# pc_kalam.net
KiCad netlist of a schematic drawn in EAGLE
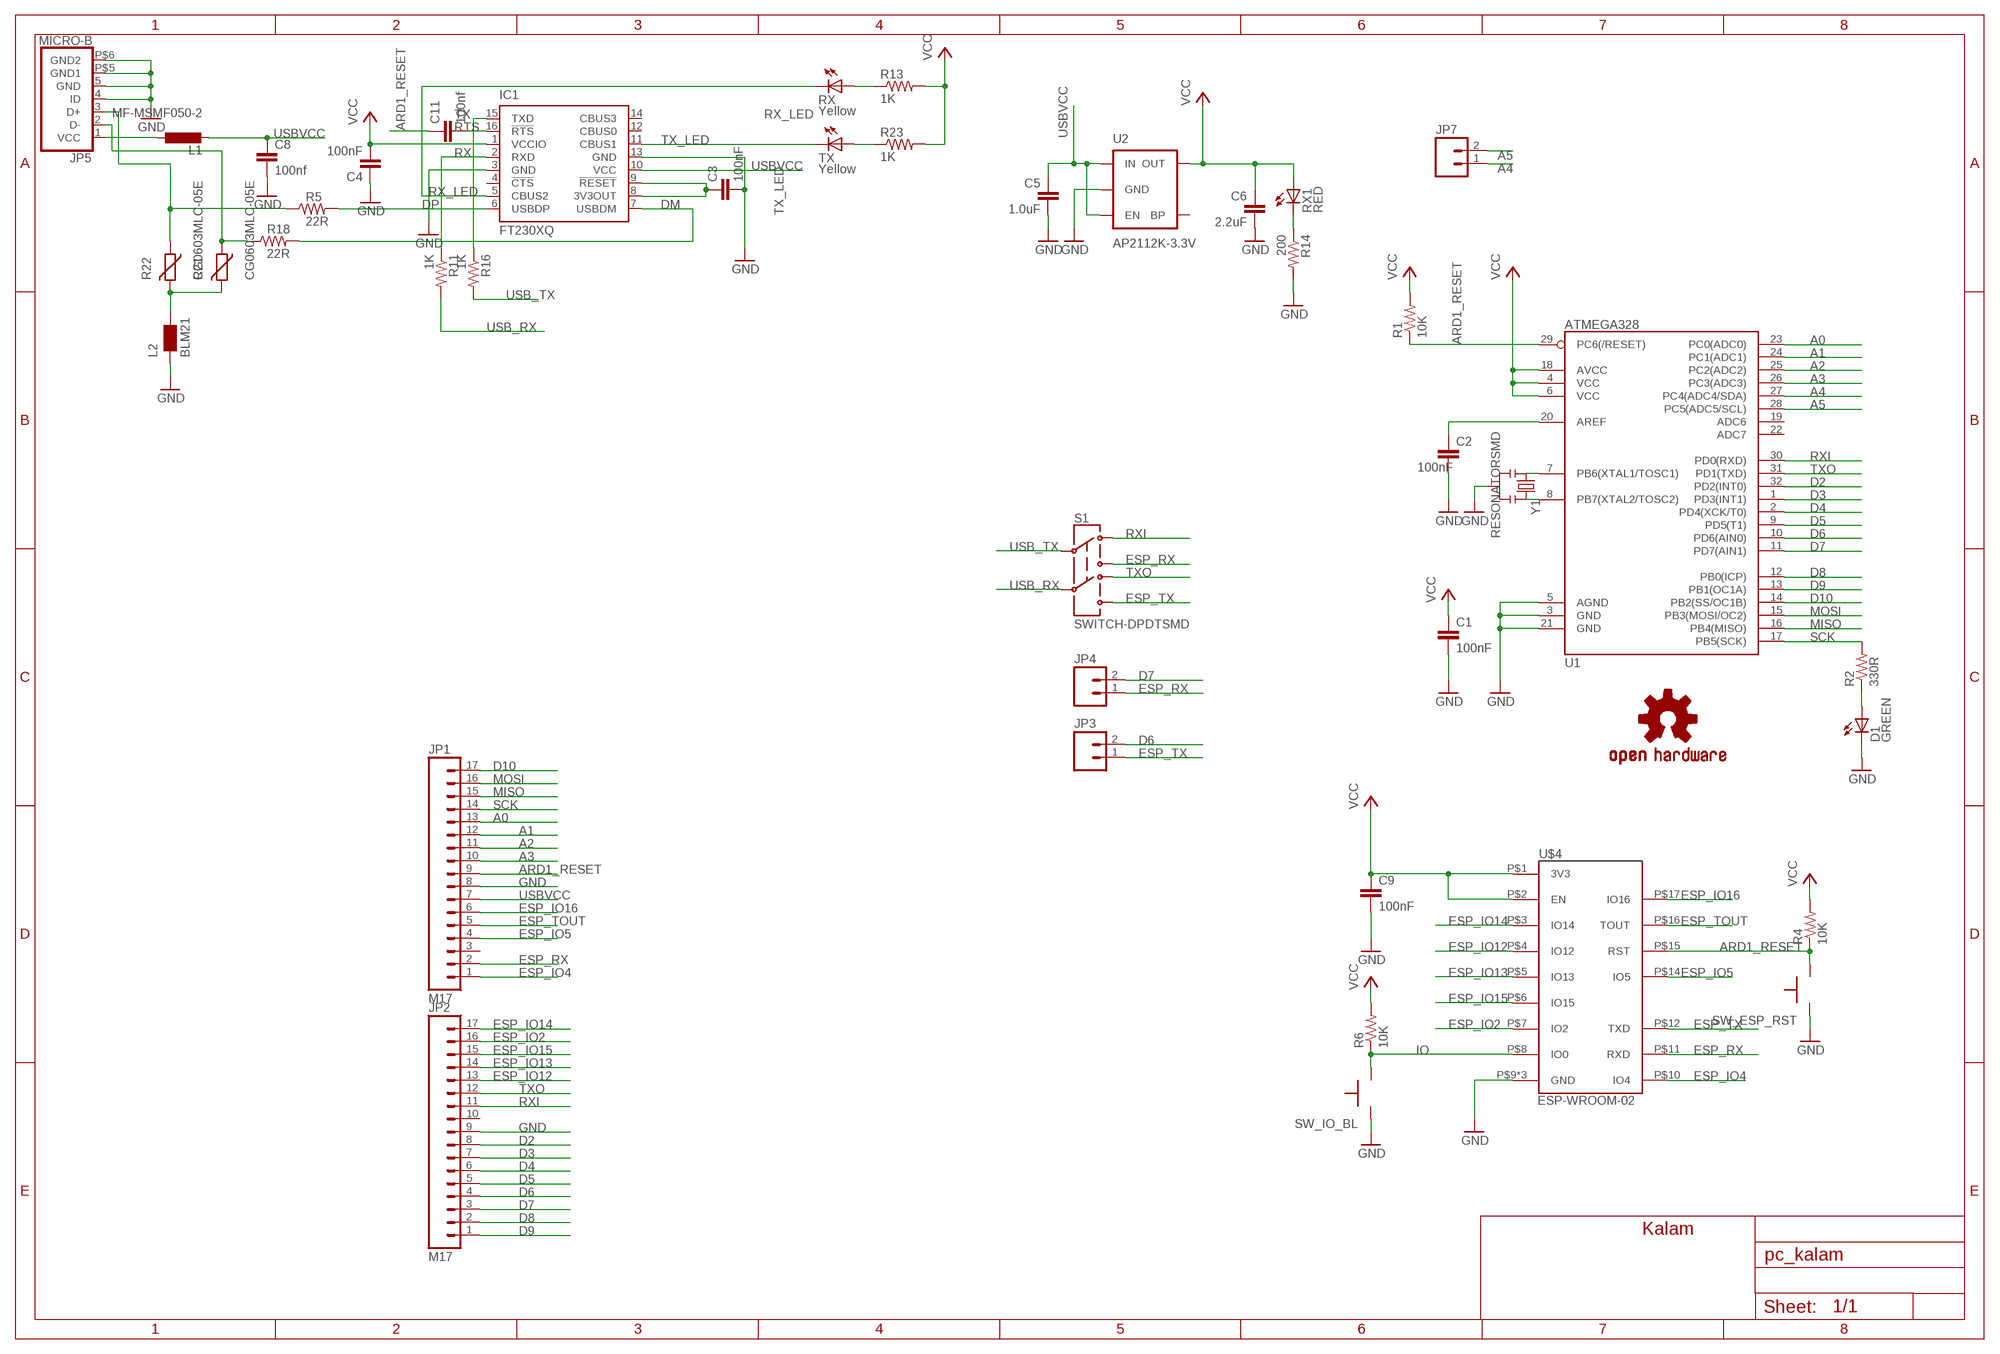
[diagram p0: schematic, sheet 1]

(export (version "E")
  (design (tool "Eeschema 10.0.6"))
  (components
    (comp (ref "C1")
      (value "100nF")
      (footprint "eagle-import:C0402")
      (libsource (lib "eagle-import") (part "C-EUC0402"))
    )
    (comp (ref "C2")
      (value "100nF")
      (footprint "eagle-import:C0402")
      (libsource (lib "eagle-import") (part "C-EUC0402"))
    )
    (comp (ref "C3")
      (value "100nF")
      (footprint "eagle-import:C0805")
      (libsource (lib "eagle-import") (part "C-EUC0805"))
    )
    (comp (ref "C4")
      (value "100nF")
      (footprint "eagle-import:C0805")
      (libsource (lib "eagle-import") (part "C-EUC0805"))
    )
    (comp (ref "C5")
      (value "1.0uF")
      (footprint "eagle-import:0805")
      (libsource (lib "eagle-import") (part "1.0UF-25V-+80/-20(0805)"))
    )
    (comp (ref "C6")
      (value "2.2uF")
      (footprint "eagle-import:C0805")
      (libsource (lib "eagle-import") (part "C-EUC0805"))
    )
    (comp (ref "C8")
      (value "100nf")
      (footprint "eagle-import:C0805")
      (libsource (lib "eagle-import") (part "C-EUC0805"))
    )
    (comp (ref "C9")
      (value "100nF")
      (footprint "eagle-import:C0402")
      (libsource (lib "eagle-import") (part "C-EUC0402"))
    )
    (comp (ref "C11")
      (value "100nf")
      (footprint "eagle-import:C0805")
      (libsource (lib "eagle-import") (part "C-EUC0805"))
    )
    (comp (ref "D1")
      (value "GREEN")
      (footprint "eagle-import:LED-0603")
      (libsource (lib "eagle-import") (part "LED0603"))
    )
    (comp (ref "IC1")
      (value "FT230XQ")
      (footprint "eagle-import:QFN16")
      (libsource (lib "eagle-import") (part "FT230XQ"))
    )
    (comp (ref "JP1")
      (value "M17")
      (footprint "eagle-import:1X17")
      (libsource (lib "eagle-import") (part "M17"))
    )
    (comp (ref "JP2")
      (value "M17")
      (footprint "eagle-import:1X17")
      (libsource (lib "eagle-import") (part "M17"))
    )
    (comp (ref "JP3")
      (value "M02PTH")
      (footprint "eagle-import:1X02")
      (libsource (lib "eagle-import") (part "M02PTH"))
    )
    (comp (ref "JP4")
      (value "M02PTH")
      (footprint "eagle-import:1X02")
      (libsource (lib "eagle-import") (part "M02PTH"))
    )
    (comp (ref "JP5")
      (value "MICRO-B")
      (footprint "eagle-import:MICRO-B")
      (libsource (lib "eagle-import") (part "MICRO-B"))
    )
    (comp (ref "JP7")
      (value "M02PTH")
      (footprint "eagle-import:1X02")
      (libsource (lib "eagle-import") (part "M02PTH"))
    )
    (comp (ref "L1")
      (value "MF-MSMF050-2")
      (footprint "eagle-import:L1812")
      (libsource (lib "eagle-import") (part "L-EUL1812"))
    )
    (comp (ref "L2")
      (value "BLM21")
      (footprint "eagle-import:0805")
      (libsource (lib "eagle-import") (part "WE-CBF_0805"))
    )
    (comp (ref "R1")
      (value "10K")
      (footprint "eagle-import:R0402")
      (libsource (lib "eagle-import") (part "R-US_R0402"))
    )
    (comp (ref "R2")
      (value "330R")
      (footprint "eagle-import:R0402")
      (libsource (lib "eagle-import") (part "R-US_R0402"))
    )
    (comp (ref "R4")
      (value "10K")
      (footprint "eagle-import:R0402")
      (libsource (lib "eagle-import") (part "R-US_R0402"))
    )
    (comp (ref "R5")
      (value "22R")
      (footprint "eagle-import:R0805")
      (libsource (lib "eagle-import") (part "R-US_R0805"))
    )
    (comp (ref "R6")
      (value "10K")
      (footprint "eagle-import:R0402")
      (libsource (lib "eagle-import") (part "R-US_R0402"))
    )
    (comp (ref "R11")
      (value "1K")
      (footprint "eagle-import:R0805")
      (libsource (lib "eagle-import") (part "R-US_R0805"))
    )
    (comp (ref "R13")
      (value "1K")
      (footprint "eagle-import:R0805")
      (libsource (lib "eagle-import") (part "R-US_R0805"))
    )
    (comp (ref "R14")
      (value "200")
      (footprint "eagle-import:R0805")
      (libsource (lib "eagle-import") (part "R-US_R0805"))
    )
    (comp (ref "R16")
      (value "1K")
      (footprint "eagle-import:R0805")
      (libsource (lib "eagle-import") (part "R-US_R0805"))
    )
    (comp (ref "R18")
      (value "22R")
      (footprint "eagle-import:R0805")
      (libsource (lib "eagle-import") (part "R-US_R0805"))
    )
    (comp (ref "R21")
      (value "CG0603MLC-05E")
      (footprint "eagle-import:CT_CN0603")
      (libsource (lib "eagle-import") (part "VARISTORCN0603"))
    )
    (comp (ref "R22")
      (value "CG0603MLC-05E")
      (footprint "eagle-import:CT_CN0603")
      (libsource (lib "eagle-import") (part "VARISTORCN0603"))
    )
    (comp (ref "R23")
      (value "1K")
      (footprint "eagle-import:R0805")
      (libsource (lib "eagle-import") (part "R-US_R0805"))
    )
    (comp (ref "RX")
      (value "Yellow")
      (footprint "eagle-import:CHIPLED_0603")
      (libsource (lib "eagle-import") (part "LEDCHIPLED_0603"))
    )
    (comp (ref "RX1")
      (value "RED")
      (footprint "eagle-import:CHIPLED_0603")
      (libsource (lib "eagle-import") (part "LEDCHIPLED_0603"))
    )
    (comp (ref "S1")
      (value "SWITCH-DPDTSMD")
      (footprint "eagle-import:AYZ0202")
      (libsource (lib "eagle-import") (part "SWITCH-DPDTSMD"))
    )
    (comp (ref "SW_ESP_RST")
      (value "B3U-1000P")
      (footprint "eagle-import:B3U-1000P")
      (libsource (lib "eagle-import") (part "B3U-1000P"))
    )
    (comp (ref "SW_IO_BL")
      (value "B3U-1000P")
      (footprint "eagle-import:B3U-1000P")
      (libsource (lib "eagle-import") (part "B3U-1000P"))
    )
    (comp (ref "TX")
      (value "Yellow")
      (footprint "eagle-import:CHIPLED_0603")
      (libsource (lib "eagle-import") (part "LEDCHIPLED_0603"))
    )
    (comp (ref "U$1")
      (value "OSHW-LOGOS")
      (footprint "eagle-import:OSHW-LOGO-S")
      (libsource (lib "eagle-import") (part "OSHW-LOGOS"))
    )
    (comp (ref "U$2")
      (value "PROTY-LOGO")
      (footprint "eagle-import:LOGO-PROTY")
      (libsource (lib "eagle-import") (part "PROTY-LOGO"))
    )
    (comp (ref "U$3")
      (value "PROTY-LOGO")
      (footprint "eagle-import:LOGO-PROTY")
      (libsource (lib "eagle-import") (part "PROTY-LOGO"))
    )
    (comp (ref "U$4")
      (value "ESP-WROOM-02")
      (footprint "eagle-import:ESP-WROOM-02")
      (libsource (lib "eagle-import") (part "ESP-WROOM-02"))
    )
    (comp (ref "U$5")
      (value "KALAM")
      (footprint "eagle-import:KALAM")
      (libsource (lib "eagle-import") (part "KALAM"))
    )
    (comp (ref "U1")
      (value "ATMEGA328")
      (footprint "eagle-import:TQFP32-08")
      (libsource (lib "eagle-import") (part "ATMEGA168"))
    )
    (comp (ref "U2")
      (value "AP2112K-3.3V")
      (footprint "eagle-import:SOT23-5")
      (libsource (lib "eagle-import") (part "V_REG_LDOSMD"))
    )
    (comp (ref "Y1")
      (value "RESONATORSMD")
      (footprint "eagle-import:RESONATOR-SMD")
      (libsource (lib "eagle-import") (part "RESONATORSMD"))
    )
  )
  (nets
    (net (code "1") (name "/A0") (class "Default")
      (node (ref "JP1") (pin "13") (pinfunction "13_13") (pintype "passive"))
      (node (ref "U1") (pin "23") (pinfunction "PC0(ADC0)_23") (pintype "bidirectional"))
    )
    (net (code "2") (name "/A1") (class "Default")
      (node (ref "JP1") (pin "12") (pinfunction "12_12") (pintype "passive"))
      (node (ref "U1") (pin "24") (pinfunction "PC1(ADC1)_24") (pintype "bidirectional"))
    )
    (net (code "3") (name "/A2") (class "Default")
      (node (ref "JP1") (pin "11") (pinfunction "11_11") (pintype "passive"))
      (node (ref "U1") (pin "25") (pinfunction "PC2(ADC2)_25") (pintype "bidirectional"))
    )
    (net (code "4") (name "/A3") (class "Default")
      (node (ref "JP1") (pin "10") (pinfunction "10_10") (pintype "passive"))
      (node (ref "U1") (pin "26") (pinfunction "PC3(ADC3)_26") (pintype "bidirectional"))
    )
    (net (code "5") (name "/A4") (class "Default")
      (node (ref "JP7") (pin "1") (pinfunction "1_1") (pintype "passive"))
      (node (ref "U1") (pin "27") (pinfunction "PC4(ADC4/SDA)_27") (pintype "bidirectional"))
    )
    (net (code "6") (name "/A5") (class "Default")
      (node (ref "JP7") (pin "2") (pinfunction "2_2") (pintype "passive"))
      (node (ref "U1") (pin "28") (pinfunction "PC5(ADC5/SCL)_28") (pintype "bidirectional"))
    )
    (net (code "7") (name "/ARD1_RESET") (class "Default")
      (node (ref "C11") (pin "1") (pinfunction "1_1") (pintype "passive"))
      (node (ref "JP1") (pin "9") (pinfunction "9_9") (pintype "passive"))
      (node (ref "R1") (pin "1") (pinfunction "1_1") (pintype "passive"))
      (node (ref "R4") (pin "1") (pinfunction "1_1") (pintype "passive"))
      (node (ref "SW_ESP_RST") (pin "P$2") (pinfunction "P$2_P$2") (pintype "bidirectional"))
      (node (ref "U$4") (pin "P$15") (pinfunction "RST_P$15") (pintype "bidirectional"))
      (node (ref "U1") (pin "29") (pinfunction "PC6(/RESET)_29") (pintype "bidirectional"))
    )
    (net (code "8") (name "/D2") (class "Default")
      (node (ref "JP2") (pin "8") (pinfunction "8_8") (pintype "passive"))
      (node (ref "U1") (pin "32") (pinfunction "PD2(INT0)_32") (pintype "bidirectional"))
    )
    (net (code "9") (name "/D3") (class "Default")
      (node (ref "JP2") (pin "7") (pinfunction "7_7") (pintype "passive"))
      (node (ref "U1") (pin "1") (pinfunction "PD3(INT1)_1") (pintype "bidirectional"))
    )
    (net (code "10") (name "/D4") (class "Default")
      (node (ref "JP2") (pin "6") (pinfunction "6_6") (pintype "passive"))
      (node (ref "U1") (pin "2") (pinfunction "PD4(XCK/T0)_2") (pintype "bidirectional"))
    )
    (net (code "11") (name "/D5") (class "Default")
      (node (ref "JP2") (pin "5") (pinfunction "5_5") (pintype "passive"))
      (node (ref "U1") (pin "9") (pinfunction "PD5(T1)_9") (pintype "bidirectional"))
    )
    (net (code "12") (name "/D6") (class "Default")
      (node (ref "JP2") (pin "4") (pinfunction "4_4") (pintype "passive"))
      (node (ref "JP3") (pin "2") (pinfunction "2_2") (pintype "passive"))
      (node (ref "U1") (pin "10") (pinfunction "PD6(AIN0)_10") (pintype "bidirectional"))
    )
    (net (code "13") (name "/D7") (class "Default")
      (node (ref "JP2") (pin "3") (pinfunction "3_3") (pintype "passive"))
      (node (ref "JP4") (pin "2") (pinfunction "2_2") (pintype "passive"))
      (node (ref "U1") (pin "11") (pinfunction "PD7(AIN1)_11") (pintype "bidirectional"))
    )
    (net (code "14") (name "/D8") (class "Default")
      (node (ref "JP2") (pin "2") (pinfunction "2_2") (pintype "passive"))
      (node (ref "U1") (pin "12") (pinfunction "PB0(ICP)_12") (pintype "bidirectional"))
    )
    (net (code "15") (name "/D9") (class "Default")
      (node (ref "JP2") (pin "1") (pinfunction "1_1") (pintype "passive"))
      (node (ref "U1") (pin "13") (pinfunction "PB1(OC1A)_13") (pintype "bidirectional"))
    )
    (net (code "16") (name "/D10") (class "Default")
      (node (ref "JP1") (pin "17") (pinfunction "17_17") (pintype "passive"))
      (node (ref "U1") (pin "14") (pinfunction "PB2(SS/OC1B)_14") (pintype "bidirectional"))
    )
    (net (code "17") (name "/DM") (class "Default")
      (node (ref "IC1") (pin "7") (pinfunction "USBDM_7") (pintype "input"))
      (node (ref "R18") (pin "2") (pinfunction "2_2") (pintype "passive"))
    )
    (net (code "18") (name "/DP") (class "Default")
      (node (ref "IC1") (pin "6") (pinfunction "USBDP_6") (pintype "input"))
      (node (ref "R5") (pin "2") (pinfunction "2_2") (pintype "passive"))
    )
    (net (code "19") (name "/ESP_IO2") (class "Default")
      (node (ref "JP2") (pin "16") (pinfunction "16_16") (pintype "passive"))
      (node (ref "U$4") (pin "P$7") (pinfunction "IO2_P$7") (pintype "bidirectional"))
    )
    (net (code "20") (name "/ESP_IO4") (class "Default")
      (node (ref "JP1") (pin "1") (pinfunction "1_1") (pintype "passive"))
      (node (ref "U$4") (pin "P$10") (pinfunction "IO4_P$10") (pintype "bidirectional"))
    )
    (net (code "21") (name "/ESP_IO5") (class "Default")
      (node (ref "JP1") (pin "4") (pinfunction "4_4") (pintype "passive"))
      (node (ref "U$4") (pin "P$14") (pinfunction "IO5_P$14") (pintype "bidirectional"))
    )
    (net (code "22") (name "/ESP_IO12") (class "Default")
      (node (ref "JP2") (pin "13") (pinfunction "13_13") (pintype "passive"))
      (node (ref "U$4") (pin "P$4") (pinfunction "IO12_P$4") (pintype "bidirectional"))
    )
    (net (code "23") (name "/ESP_IO13") (class "Default")
      (node (ref "JP2") (pin "14") (pinfunction "14_14") (pintype "passive"))
      (node (ref "U$4") (pin "P$5") (pinfunction "IO13_P$5") (pintype "bidirectional"))
    )
    (net (code "24") (name "/ESP_IO14") (class "Default")
      (node (ref "JP2") (pin "17") (pinfunction "17_17") (pintype "passive"))
      (node (ref "U$4") (pin "P$3") (pinfunction "IO14_P$3") (pintype "bidirectional"))
    )
    (net (code "25") (name "/ESP_IO15") (class "Default")
      (node (ref "JP2") (pin "15") (pinfunction "15_15") (pintype "passive"))
      (node (ref "U$4") (pin "P$6") (pinfunction "IO15_P$6") (pintype "bidirectional"))
    )
    (net (code "26") (name "/ESP_IO16") (class "Default")
      (node (ref "JP1") (pin "6") (pinfunction "6_6") (pintype "passive"))
      (node (ref "U$4") (pin "P$17") (pinfunction "IO16_P$17") (pintype "bidirectional"))
    )
    (net (code "27") (name "/ESP_RX") (class "Default")
      (node (ref "JP1") (pin "2") (pinfunction "2_2") (pintype "passive"))
      (node (ref "JP4") (pin "1") (pinfunction "1_1") (pintype "passive"))
      (node (ref "S1") (pin "3") (pinfunction "3_3") (pintype "bidirectional"))
      (node (ref "U$4") (pin "P$11") (pinfunction "RXD_P$11") (pintype "input"))
    )
    (net (code "28") (name "/ESP_TOUT") (class "Default")
      (node (ref "JP1") (pin "5") (pinfunction "5_5") (pintype "passive"))
      (node (ref "U$4") (pin "P$16") (pinfunction "TOUT_P$16") (pintype "bidirectional"))
    )
    (net (code "29") (name "/ESP_TX") (class "Default")
      (node (ref "JP3") (pin "1") (pinfunction "1_1") (pintype "passive"))
      (node (ref "S1") (pin "6") (pinfunction "6_6") (pintype "bidirectional"))
      (node (ref "U$4") (pin "P$12") (pinfunction "TXD_P$12") (pintype "output"))
    )
    (net (code "30") (name "/IO") (class "Default")
      (node (ref "R6") (pin "1") (pinfunction "1_1") (pintype "passive"))
      (node (ref "SW_IO_BL") (pin "P$2") (pinfunction "P$2_P$2") (pintype "bidirectional"))
      (node (ref "U$4") (pin "P$8") (pinfunction "IO0_P$8") (pintype "bidirectional"))
    )
    (net (code "31") (name "/MISO") (class "Default")
      (node (ref "JP1") (pin "15") (pinfunction "15_15") (pintype "passive"))
      (node (ref "U1") (pin "16") (pinfunction "PB4(MISO)_16") (pintype "bidirectional"))
    )
    (net (code "32") (name "/MOSI") (class "Default")
      (node (ref "JP1") (pin "16") (pinfunction "16_16") (pintype "passive"))
      (node (ref "U1") (pin "15") (pinfunction "PB3(MOSI/OC2)_15") (pintype "bidirectional"))
    )
    (net (code "33") (name "/RTS") (class "Default")
      (node (ref "C11") (pin "2") (pinfunction "2_2") (pintype "passive"))
      (node (ref "IC1") (pin "16") (pinfunction "~{RTS}_16") (pintype "output"))
    )
    (net (code "34") (name "/RX") (class "Default")
      (node (ref "IC1") (pin "2") (pinfunction "RXD_2") (pintype "input"))
      (node (ref "R11") (pin "1") (pinfunction "1_1") (pintype "passive"))
    )
    (net (code "35") (name "/RXI") (class "Default")
      (node (ref "JP2") (pin "11") (pinfunction "11_11") (pintype "passive"))
      (node (ref "S1") (pin "1") (pinfunction "1_1") (pintype "bidirectional"))
      (node (ref "U1") (pin "30") (pinfunction "PD0(RXD)_30") (pintype "bidirectional"))
    )
    (net (code "36") (name "/RX_LED") (class "Default")
      (node (ref "IC1") (pin "5") (pinfunction "CBUS2_5") (pintype "bidirectional"))
      (node (ref "RX") (pin "C") (pinfunction "C_C") (pintype "passive"))
    )
    (net (code "37") (name "/SCK") (class "Default")
      (node (ref "JP1") (pin "14") (pinfunction "14_14") (pintype "passive"))
      (node (ref "R2") (pin "2") (pinfunction "2_2") (pintype "passive"))
      (node (ref "U1") (pin "17") (pinfunction "PB5(SCK)_17") (pintype "bidirectional"))
    )
    (net (code "38") (name "/TX") (class "Default")
      (node (ref "IC1") (pin "15") (pinfunction "TXD_15") (pintype "output"))
      (node (ref "R16") (pin "1") (pinfunction "1_1") (pintype "passive"))
    )
    (net (code "39") (name "/TXO") (class "Default")
      (node (ref "JP2") (pin "12") (pinfunction "12_12") (pintype "passive"))
      (node (ref "S1") (pin "4") (pinfunction "4_4") (pintype "bidirectional"))
      (node (ref "U1") (pin "31") (pinfunction "PD1(TXD)_31") (pintype "bidirectional"))
    )
    (net (code "40") (name "/TX_LED") (class "Default")
      (node (ref "IC1") (pin "11") (pinfunction "CBUS1_11") (pintype "bidirectional"))
      (node (ref "TX") (pin "C") (pinfunction "C_C") (pintype "passive"))
    )
    (net (code "41") (name "/USBVCC") (class "Default")
      (node (ref "C5") (pin "1") (pinfunction "1_1") (pintype "passive"))
      (node (ref "C8") (pin "1") (pinfunction "1_1") (pintype "passive"))
      (node (ref "IC1") (pin "10") (pinfunction "VCC_10") (pintype "power_in"))
      (node (ref "JP1") (pin "7") (pinfunction "7_7") (pintype "passive"))
      (node (ref "L1") (pin "2") (pinfunction "2_2") (pintype "passive"))
      (node (ref "U2") (pin "1") (pinfunction "IN_1") (pintype "input"))
      (node (ref "U2") (pin "3") (pinfunction "EN_3") (pintype "input"))
    )
    (net (code "42") (name "/USB_RX") (class "Default")
      (node (ref "R11") (pin "2") (pinfunction "2_2") (pintype "passive"))
      (node (ref "S1") (pin "5") (pinfunction "5_5") (pintype "bidirectional"))
    )
    (net (code "43") (name "/USB_TX") (class "Default")
      (node (ref "R16") (pin "2") (pinfunction "2_2") (pintype "passive"))
      (node (ref "S1") (pin "2") (pinfunction "2_2") (pintype "bidirectional"))
    )
    (net (code "44") (name "GND") (class "Default")
      (node (ref "C1") (pin "2") (pinfunction "2_2") (pintype "passive"))
      (node (ref "C2") (pin "2") (pinfunction "2_2") (pintype "passive"))
      (node (ref "C3") (pin "2") (pinfunction "2_2") (pintype "passive"))
      (node (ref "C4") (pin "1") (pinfunction "1_1") (pintype "passive"))
      (node (ref "C5") (pin "2") (pinfunction "2_2") (pintype "passive"))
      (node (ref "C6") (pin "2") (pinfunction "2_2") (pintype "passive"))
      (node (ref "C8") (pin "2") (pinfunction "2_2") (pintype "passive"))
      (node (ref "C9") (pin "2") (pinfunction "2_2") (pintype "passive"))
      (node (ref "D1") (pin "C") (pinfunction "C_C") (pintype "passive"))
      (node (ref "IC1") (pin "13") (pinfunction "GND_13") (pintype "power_in"))
      (node (ref "IC1") (pin "3") (pinfunction "GND_3") (pintype "power_in"))
      (node (ref "JP1") (pin "8") (pinfunction "8_8") (pintype "passive"))
      (node (ref "JP2") (pin "9") (pinfunction "9_9") (pintype "passive"))
      (node (ref "JP5") (pin "4") (pinfunction "ID_4") (pintype "bidirectional"))
      (node (ref "JP5") (pin "5") (pinfunction "GND_5") (pintype "bidirectional"))
      (node (ref "JP5") (pin "P$5") (pinfunction "GND1_P$5") (pintype "bidirectional"))
      (node (ref "JP5") (pin "P$6") (pinfunction "GND2_P$6") (pintype "bidirectional"))
      (node (ref "L2") (pin "1") (pinfunction "1_1") (pintype "passive"))
      (node (ref "R14") (pin "2") (pinfunction "2_2") (pintype "passive"))
      (node (ref "SW_ESP_RST") (pin "P$1") (pinfunction "P$1_P$1") (pintype "bidirectional"))
      (node (ref "SW_IO_BL") (pin "P$1") (pinfunction "P$1_P$1") (pintype "bidirectional"))
      (node (ref "U$4") (pin "P$13") (pinfunction "GND_P$13") (pintype "power_in"))
      (node (ref "U$4") (pin "P$18") (pinfunction "GND_P$18") (pintype "power_in"))
      (node (ref "U$4") (pin "P$9") (pinfunction "GND_P$9") (pintype "power_in"))
      (node (ref "U1") (pin "21") (pinfunction "GND_21") (pintype "bidirectional"))
      (node (ref "U1") (pin "3") (pinfunction "GND_3") (pintype "bidirectional"))
      (node (ref "U1") (pin "5") (pinfunction "AGND_5") (pintype "bidirectional"))
      (node (ref "U2") (pin "2") (pinfunction "GND_2") (pintype "input"))
      (node (ref "Y1") (pin "2") (pinfunction "2_2") (pintype "passive"))
    )
    (net (code "45") (name "Net-(D1-PadA)") (class "Default")
      (node (ref "D1") (pin "A") (pinfunction "A_A") (pintype "passive"))
      (node (ref "R2") (pin "1") (pinfunction "1_1") (pintype "passive"))
    )
    (net (code "46") (name "Net-(IC1-3V3OUT)") (class "Default")
      (node (ref "C3") (pin "1") (pinfunction "1_1") (pintype "passive"))
      (node (ref "IC1") (pin "8") (pinfunction "3V3OUT_8") (pintype "output"))
      (node (ref "IC1") (pin "9") (pinfunction "~{RESET}_9") (pintype "input"))
    )
    (net (code "47") (name "Net-(JP5-D+)") (class "Default")
      (node (ref "JP5") (pin "3") (pinfunction "D+_3") (pintype "bidirectional"))
      (node (ref "R22") (pin "1") (pinfunction "1_1") (pintype "passive"))
      (node (ref "R5") (pin "1") (pinfunction "1_1") (pintype "passive"))
    )
    (net (code "48") (name "Net-(JP5-D-)") (class "Default")
      (node (ref "JP5") (pin "2") (pinfunction "D-_2") (pintype "bidirectional"))
      (node (ref "R18") (pin "1") (pinfunction "1_1") (pintype "passive"))
      (node (ref "R21") (pin "1") (pinfunction "1_1") (pintype "passive"))
    )
    (net (code "49") (name "Net-(JP5-VCC)") (class "Default")
      (node (ref "JP5") (pin "1") (pinfunction "VCC_1") (pintype "bidirectional"))
      (node (ref "L1") (pin "1") (pinfunction "1_1") (pintype "passive"))
    )
    (net (code "50") (name "Net-(L2-Pad2)") (class "Default")
      (node (ref "L2") (pin "2") (pinfunction "2_2") (pintype "passive"))
      (node (ref "R21") (pin "2") (pinfunction "2_2") (pintype "passive"))
      (node (ref "R22") (pin "2") (pinfunction "2_2") (pintype "passive"))
    )
    (net (code "51") (name "Net-(R13-Pad1)") (class "Default")
      (node (ref "R13") (pin "1") (pinfunction "1_1") (pintype "passive"))
      (node (ref "RX") (pin "A") (pinfunction "A_A") (pintype "passive"))
    )
    (net (code "52") (name "Net-(R14-Pad1)") (class "Default")
      (node (ref "R14") (pin "1") (pinfunction "1_1") (pintype "passive"))
      (node (ref "RX1") (pin "C") (pinfunction "C_C") (pintype "passive"))
    )
    (net (code "53") (name "Net-(R23-Pad1)") (class "Default")
      (node (ref "R23") (pin "1") (pinfunction "1_1") (pintype "passive"))
      (node (ref "TX") (pin "A") (pinfunction "A_A") (pintype "passive"))
    )
    (net (code "54") (name "Net-(U1-AREF)") (class "Default")
      (node (ref "C2") (pin "1") (pinfunction "1_1") (pintype "passive"))
      (node (ref "U1") (pin "20") (pinfunction "AREF_20") (pintype "bidirectional"))
    )
    (net (code "55") (name "Net-(U1-PB6(XTAL1{slash}TOSC1))") (class "Default")
      (node (ref "U1") (pin "7") (pinfunction "PB6(XTAL1/TOSC1)_7") (pintype "bidirectional"))
      (node (ref "Y1") (pin "1") (pinfunction "1_1") (pintype "passive"))
    )
    (net (code "56") (name "Net-(U1-PB7(XTAL2{slash}TOSC2))") (class "Default")
      (node (ref "U1") (pin "8") (pinfunction "PB7(XTAL2/TOSC2)_8") (pintype "bidirectional"))
      (node (ref "Y1") (pin "3") (pinfunction "3_3") (pintype "passive"))
    )
    (net (code "57") (name "VCC") (class "Default")
      (node (ref "C1") (pin "1") (pinfunction "1_1") (pintype "passive"))
      (node (ref "C4") (pin "2") (pinfunction "2_2") (pintype "passive"))
      (node (ref "C6") (pin "1") (pinfunction "1_1") (pintype "passive"))
      (node (ref "C9") (pin "1") (pinfunction "1_1") (pintype "passive"))
      (node (ref "IC1") (pin "1") (pinfunction "VCCIO_1") (pintype "power_in"))
      (node (ref "R1") (pin "2") (pinfunction "2_2") (pintype "passive"))
      (node (ref "R13") (pin "2") (pinfunction "2_2") (pintype "passive"))
      (node (ref "R23") (pin "2") (pinfunction "2_2") (pintype "passive"))
      (node (ref "R4") (pin "2") (pinfunction "2_2") (pintype "passive"))
      (node (ref "R6") (pin "2") (pinfunction "2_2") (pintype "passive"))
      (node (ref "RX1") (pin "A") (pinfunction "A_A") (pintype "passive"))
      (node (ref "U$4") (pin "P$1") (pinfunction "3V3_P$1") (pintype "power_in"))
      (node (ref "U$4") (pin "P$2") (pinfunction "EN_P$2") (pintype "bidirectional"))
      (node (ref "U1") (pin "18") (pinfunction "AVCC_18") (pintype "bidirectional"))
      (node (ref "U1") (pin "4") (pinfunction "VCC_4") (pintype "bidirectional"))
      (node (ref "U1") (pin "6") (pinfunction "VCC_6") (pintype "bidirectional"))
      (node (ref "U2") (pin "5") (pinfunction "OUT_5") (pintype "passive"))
    )
    (net (code "58") (name "unconnected-(IC1-CBUS0-Pad12)") (class "Default")
      (node (ref "IC1") (pin "12") (pinfunction "CBUS0_12") (pintype "bidirectional"))
    )
    (net (code "59") (name "unconnected-(IC1-CBUS3-Pad14)") (class "Default")
      (node (ref "IC1") (pin "14") (pinfunction "CBUS3_14") (pintype "bidirectional"))
    )
    (net (code "60") (name "unconnected-(IC1-~{CTS}-Pad4)") (class "Default")
      (node (ref "IC1") (pin "4") (pinfunction "~{CTS}_4") (pintype "input"))
    )
    (net (code "61") (name "unconnected-(JP1-Pad3)") (class "Default")
      (node (ref "JP1") (pin "3") (pinfunction "3_3") (pintype "passive"))
    )
    (net (code "62") (name "unconnected-(JP2-Pad10)") (class "Default")
      (node (ref "JP2") (pin "10") (pinfunction "10_10") (pintype "passive"))
    )
    (net (code "63") (name "unconnected-(U1-ADC6-Pad19)") (class "Default")
      (node (ref "U1") (pin "19") (pinfunction "ADC6_19") (pintype "bidirectional"))
    )
    (net (code "64") (name "unconnected-(U1-ADC7-Pad22)") (class "Default")
      (node (ref "U1") (pin "22") (pinfunction "ADC7_22") (pintype "bidirectional"))
    )
    (net (code "65") (name "unconnected-(U2-BP-Pad4)") (class "Default")
      (node (ref "U2") (pin "4") (pinfunction "BP_4") (pintype "input"))
    )
  )
)
